# SMI_Link_7-12.net
KiCad netlist of a schematic drawn in Altium Designer
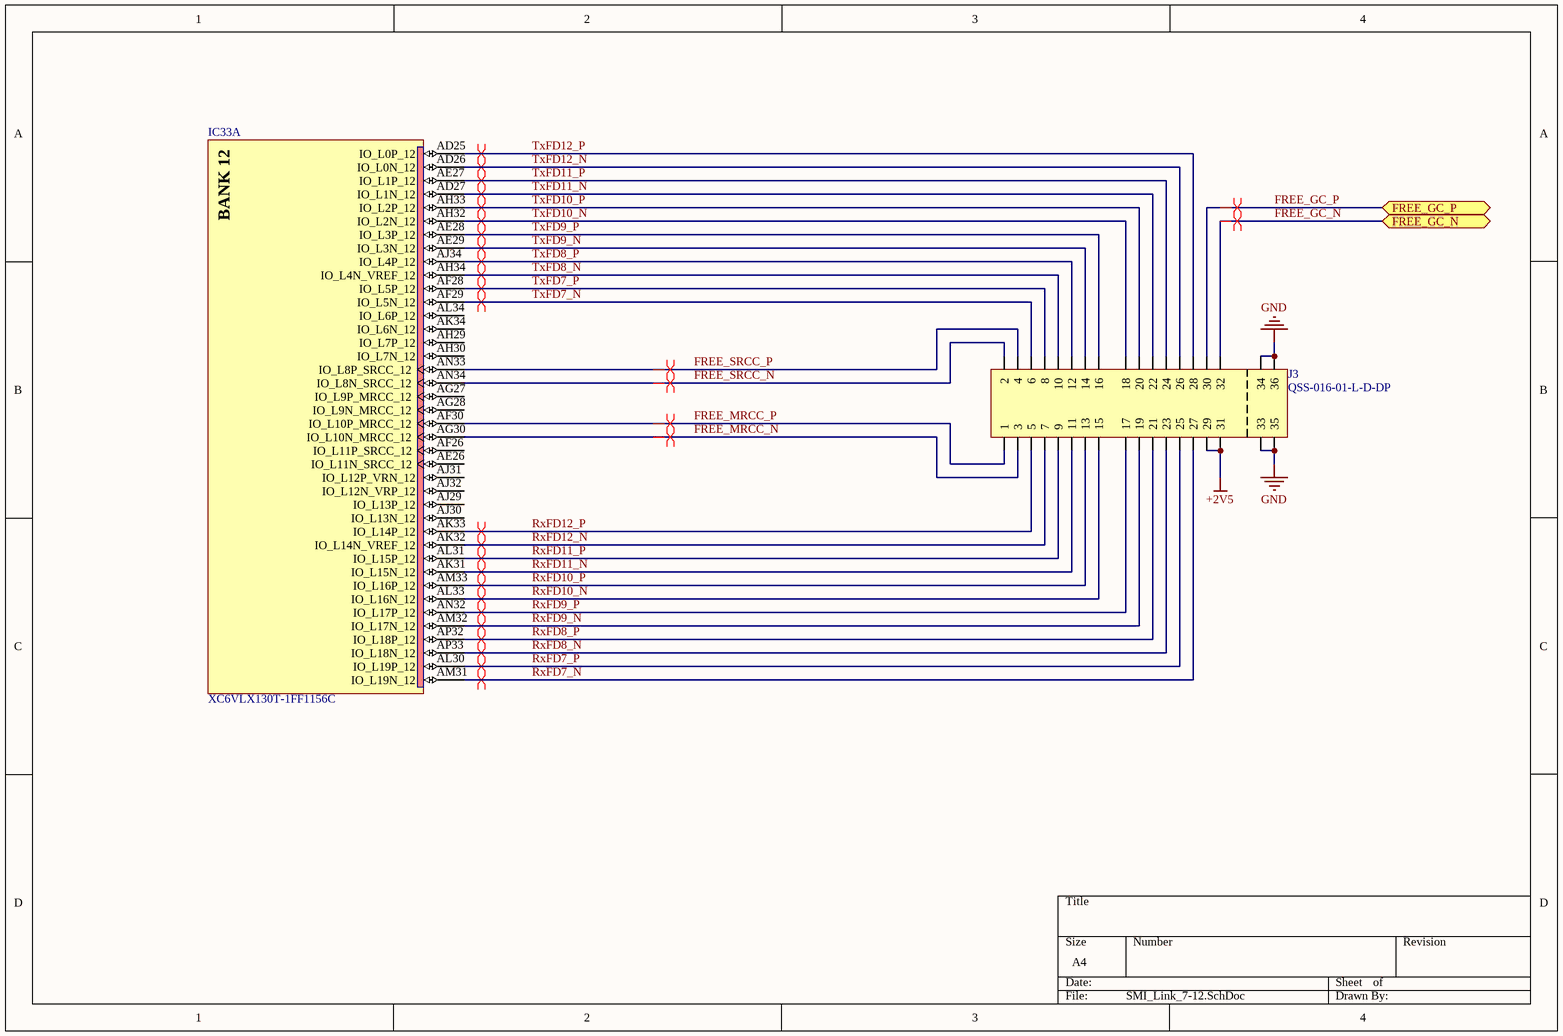
[diagram p0: SMI_Link_7-12.SchDoc]

(export (version "E")
  (design (tool "Eeschema 10.0.6"))
  (components
    (comp (ref "IC33")
      (value "XC6VLX130T-1FF1156C")
      (footprint "FF1156")
      (fields (field (name "PUBLISHER") "Altium Limited"))
      (libsource (lib "Xilinx Virtex-6") (part "XC6VLX130T-1FF1156C"))
    )
    (comp (ref "J3")
      (value "QSS-016-01-L-D-DP")
      (footprint "QSS-016-01-X-D-DP-A")
      (libsource (lib "wr_switch") (part "QSS-016-01-L-D-DP"))
    )
  )
  (nets
    (net (code "1") (name "+2V5") (class "Default")
      (node (ref "J3") (pin "29") (pinfunction "29_29") (pintype "passive"))
      (node (ref "J3") (pin "31") (pinfunction "31_31") (pintype "passive"))
    )
    (net (code "2") (name "/FREE_GC_N") (class "Default")
      (node (ref "J3") (pin "32") (pinfunction "32_32") (pintype "passive"))
    )
    (net (code "3") (name "/FREE_GC_P") (class "Default")
      (node (ref "J3") (pin "30") (pinfunction "30_30") (pintype "passive"))
    )
    (net (code "4") (name "/FREE_MRCC_N") (class "Default")
      (node (ref "IC33") (pin "AG30") (pinfunction "IO_L10N_MRCC_12_AG30") (pintype "bidirectional"))
      (node (ref "J3") (pin "3") (pinfunction "3_3") (pintype "passive"))
    )
    (net (code "5") (name "/FREE_MRCC_P") (class "Default")
      (node (ref "IC33") (pin "AF30") (pinfunction "IO_L10P_MRCC_12_AF30") (pintype "bidirectional"))
      (node (ref "J3") (pin "1") (pinfunction "1_1") (pintype "passive"))
    )
    (net (code "6") (name "/FREE_SRCC_N") (class "Default")
      (node (ref "IC33") (pin "AN34") (pinfunction "IO_L8N_SRCC_12_AN34") (pintype "bidirectional"))
      (node (ref "J3") (pin "2") (pinfunction "2_2") (pintype "passive"))
    )
    (net (code "7") (name "/FREE_SRCC_P") (class "Default")
      (node (ref "IC33") (pin "AN33") (pinfunction "IO_L8P_SRCC_12_AN33") (pintype "bidirectional"))
      (node (ref "J3") (pin "4") (pinfunction "4_4") (pintype "passive"))
    )
    (net (code "8") (name "/RxFD7_N") (class "Default")
      (node (ref "IC33") (pin "AM31") (pinfunction "IO_L19N_12_AM31") (pintype "bidirectional"))
      (node (ref "J3") (pin "27") (pinfunction "27_27") (pintype "passive"))
    )
    (net (code "9") (name "/RxFD7_P") (class "Default")
      (node (ref "IC33") (pin "AL30") (pinfunction "IO_L19P_12_AL30") (pintype "bidirectional"))
      (node (ref "J3") (pin "25") (pinfunction "25_25") (pintype "passive"))
    )
    (net (code "10") (name "/RxFD8_N") (class "Default")
      (node (ref "IC33") (pin "AP33") (pinfunction "IO_L18N_12_AP33") (pintype "bidirectional"))
      (node (ref "J3") (pin "23") (pinfunction "23_23") (pintype "passive"))
    )
    (net (code "11") (name "/RxFD8_P") (class "Default")
      (node (ref "IC33") (pin "AP32") (pinfunction "IO_L18P_12_AP32") (pintype "bidirectional"))
      (node (ref "J3") (pin "21") (pinfunction "21_21") (pintype "passive"))
    )
    (net (code "12") (name "/RxFD9_N") (class "Default")
      (node (ref "IC33") (pin "AM32") (pinfunction "IO_L17N_12_AM32") (pintype "bidirectional"))
      (node (ref "J3") (pin "19") (pinfunction "19_19") (pintype "passive"))
    )
    (net (code "13") (name "/RxFD9_P") (class "Default")
      (node (ref "IC33") (pin "AN32") (pinfunction "IO_L17P_12_AN32") (pintype "bidirectional"))
      (node (ref "J3") (pin "17") (pinfunction "17_17") (pintype "passive"))
    )
    (net (code "14") (name "/RxFD10_N") (class "Default")
      (node (ref "IC33") (pin "AL33") (pinfunction "IO_L16N_12_AL33") (pintype "bidirectional"))
      (node (ref "J3") (pin "15") (pinfunction "15_15") (pintype "passive"))
    )
    (net (code "15") (name "/RxFD10_P") (class "Default")
      (node (ref "IC33") (pin "AM33") (pinfunction "IO_L16P_12_AM33") (pintype "bidirectional"))
      (node (ref "J3") (pin "13") (pinfunction "13_13") (pintype "passive"))
    )
    (net (code "16") (name "/RxFD11_N") (class "Default")
      (node (ref "IC33") (pin "AK31") (pinfunction "IO_L15N_12_AK31") (pintype "bidirectional"))
      (node (ref "J3") (pin "11") (pinfunction "11_11") (pintype "passive"))
    )
    (net (code "17") (name "/RxFD11_P") (class "Default")
      (node (ref "IC33") (pin "AL31") (pinfunction "IO_L15P_12_AL31") (pintype "bidirectional"))
      (node (ref "J3") (pin "9") (pinfunction "9_9") (pintype "passive"))
    )
    (net (code "18") (name "/RxFD12_N") (class "Default")
      (node (ref "IC33") (pin "AK32") (pinfunction "IO_L14N_VREF_12_AK32") (pintype "bidirectional"))
      (node (ref "J3") (pin "7") (pinfunction "7_7") (pintype "passive"))
    )
    (net (code "19") (name "/RxFD12_P") (class "Default")
      (node (ref "IC33") (pin "AK33") (pinfunction "IO_L14P_12_AK33") (pintype "bidirectional"))
      (node (ref "J3") (pin "5") (pinfunction "5_5") (pintype "passive"))
    )
    (net (code "20") (name "/TxFD7_N") (class "Default")
      (node (ref "IC33") (pin "AF29") (pinfunction "IO_L5N_12_AF29") (pintype "bidirectional"))
      (node (ref "J3") (pin "6") (pinfunction "6_6") (pintype "passive"))
    )
    (net (code "21") (name "/TxFD7_P") (class "Default")
      (node (ref "IC33") (pin "AF28") (pinfunction "IO_L5P_12_AF28") (pintype "bidirectional"))
      (node (ref "J3") (pin "8") (pinfunction "8_8") (pintype "passive"))
    )
    (net (code "22") (name "/TxFD8_N") (class "Default")
      (node (ref "IC33") (pin "AH34") (pinfunction "IO_L4N_VREF_12_AH34") (pintype "bidirectional"))
      (node (ref "J3") (pin "10") (pinfunction "10_10") (pintype "passive"))
    )
    (net (code "23") (name "/TxFD8_P") (class "Default")
      (node (ref "IC33") (pin "AJ34") (pinfunction "IO_L4P_12_AJ34") (pintype "bidirectional"))
      (node (ref "J3") (pin "12") (pinfunction "12_12") (pintype "passive"))
    )
    (net (code "24") (name "/TxFD9_N") (class "Default")
      (node (ref "IC33") (pin "AE29") (pinfunction "IO_L3N_12_AE29") (pintype "bidirectional"))
      (node (ref "J3") (pin "14") (pinfunction "14_14") (pintype "passive"))
    )
    (net (code "25") (name "/TxFD9_P") (class "Default")
      (node (ref "IC33") (pin "AE28") (pinfunction "IO_L3P_12_AE28") (pintype "bidirectional"))
      (node (ref "J3") (pin "16") (pinfunction "16_16") (pintype "passive"))
    )
    (net (code "26") (name "/TxFD10_N") (class "Default")
      (node (ref "IC33") (pin "AH32") (pinfunction "IO_L2N_12_AH32") (pintype "bidirectional"))
      (node (ref "J3") (pin "18") (pinfunction "18_18") (pintype "passive"))
    )
    (net (code "27") (name "/TxFD10_P") (class "Default")
      (node (ref "IC33") (pin "AH33") (pinfunction "IO_L2P_12_AH33") (pintype "bidirectional"))
      (node (ref "J3") (pin "20") (pinfunction "20_20") (pintype "passive"))
    )
    (net (code "28") (name "/TxFD11_N") (class "Default")
      (node (ref "IC33") (pin "AD27") (pinfunction "IO_L1N_12_AD27") (pintype "bidirectional"))
      (node (ref "J3") (pin "22") (pinfunction "22_22") (pintype "passive"))
    )
    (net (code "29") (name "/TxFD11_P") (class "Default")
      (node (ref "IC33") (pin "AE27") (pinfunction "IO_L1P_12_AE27") (pintype "bidirectional"))
      (node (ref "J3") (pin "24") (pinfunction "24_24") (pintype "passive"))
    )
    (net (code "30") (name "/TxFD12_N") (class "Default")
      (node (ref "IC33") (pin "AD26") (pinfunction "IO_L0N_12_AD26") (pintype "bidirectional"))
      (node (ref "J3") (pin "26") (pinfunction "26_26") (pintype "passive"))
    )
    (net (code "31") (name "/TxFD12_P") (class "Default")
      (node (ref "IC33") (pin "AD25") (pinfunction "IO_L0P_12_AD25") (pintype "bidirectional"))
      (node (ref "J3") (pin "28") (pinfunction "28_28") (pintype "passive"))
    )
    (net (code "32") (name "GND") (class "Default")
      (node (ref "J3") (pin "33") (pinfunction "33_33") (pintype "passive"))
      (node (ref "J3") (pin "34") (pinfunction "34_34") (pintype "passive"))
      (node (ref "J3") (pin "35") (pinfunction "35_35") (pintype "passive"))
      (node (ref "J3") (pin "36") (pinfunction "36_36") (pintype "passive"))
    )
    (net (code "33") (name "unconnected-(IC33A-IO_L6N_12-PadAK34)") (class "Default")
      (node (ref "IC33") (pin "AK34") (pinfunction "IO_L6N_12_AK34") (pintype "bidirectional"))
    )
    (net (code "34") (name "unconnected-(IC33A-IO_L6P_12-PadAL34)") (class "Default")
      (node (ref "IC33") (pin "AL34") (pinfunction "IO_L6P_12_AL34") (pintype "bidirectional"))
    )
    (net (code "35") (name "unconnected-(IC33A-IO_L7N_12-PadAH30)") (class "Default")
      (node (ref "IC33") (pin "AH30") (pinfunction "IO_L7N_12_AH30") (pintype "bidirectional"))
    )
    (net (code "36") (name "unconnected-(IC33A-IO_L7P_12-PadAH29)") (class "Default")
      (node (ref "IC33") (pin "AH29") (pinfunction "IO_L7P_12_AH29") (pintype "bidirectional"))
    )
    (net (code "37") (name "unconnected-(IC33A-IO_L9N_MRCC_12-PadAG28)") (class "Default")
      (node (ref "IC33") (pin "AG28") (pinfunction "IO_L9N_MRCC_12_AG28") (pintype "bidirectional"))
    )
    (net (code "38") (name "unconnected-(IC33A-IO_L9P_MRCC_12-PadAG27)") (class "Default")
      (node (ref "IC33") (pin "AG27") (pinfunction "IO_L9P_MRCC_12_AG27") (pintype "bidirectional"))
    )
    (net (code "39") (name "unconnected-(IC33A-IO_L11N_SRCC_12-PadAE26)") (class "Default")
      (node (ref "IC33") (pin "AE26") (pinfunction "IO_L11N_SRCC_12_AE26") (pintype "bidirectional"))
    )
    (net (code "40") (name "unconnected-(IC33A-IO_L11P_SRCC_12-PadAF26)") (class "Default")
      (node (ref "IC33") (pin "AF26") (pinfunction "IO_L11P_SRCC_12_AF26") (pintype "bidirectional"))
    )
    (net (code "41") (name "unconnected-(IC33A-IO_L12N_VRP_12-PadAJ32)") (class "Default")
      (node (ref "IC33") (pin "AJ32") (pinfunction "IO_L12N_VRP_12_AJ32") (pintype "bidirectional"))
    )
    (net (code "42") (name "unconnected-(IC33A-IO_L12P_VRN_12-PadAJ31)") (class "Default")
      (node (ref "IC33") (pin "AJ31") (pinfunction "IO_L12P_VRN_12_AJ31") (pintype "bidirectional"))
    )
    (net (code "43") (name "unconnected-(IC33A-IO_L13N_12-PadAJ30)") (class "Default")
      (node (ref "IC33") (pin "AJ30") (pinfunction "IO_L13N_12_AJ30") (pintype "bidirectional"))
    )
    (net (code "44") (name "unconnected-(IC33A-IO_L13P_12-PadAJ29)") (class "Default")
      (node (ref "IC33") (pin "AJ29") (pinfunction "IO_L13P_12_AJ29") (pintype "bidirectional"))
    )
  )
)
